# 08_Power_Switch.net
KiCad netlist of a schematic drawn in Altium Designer
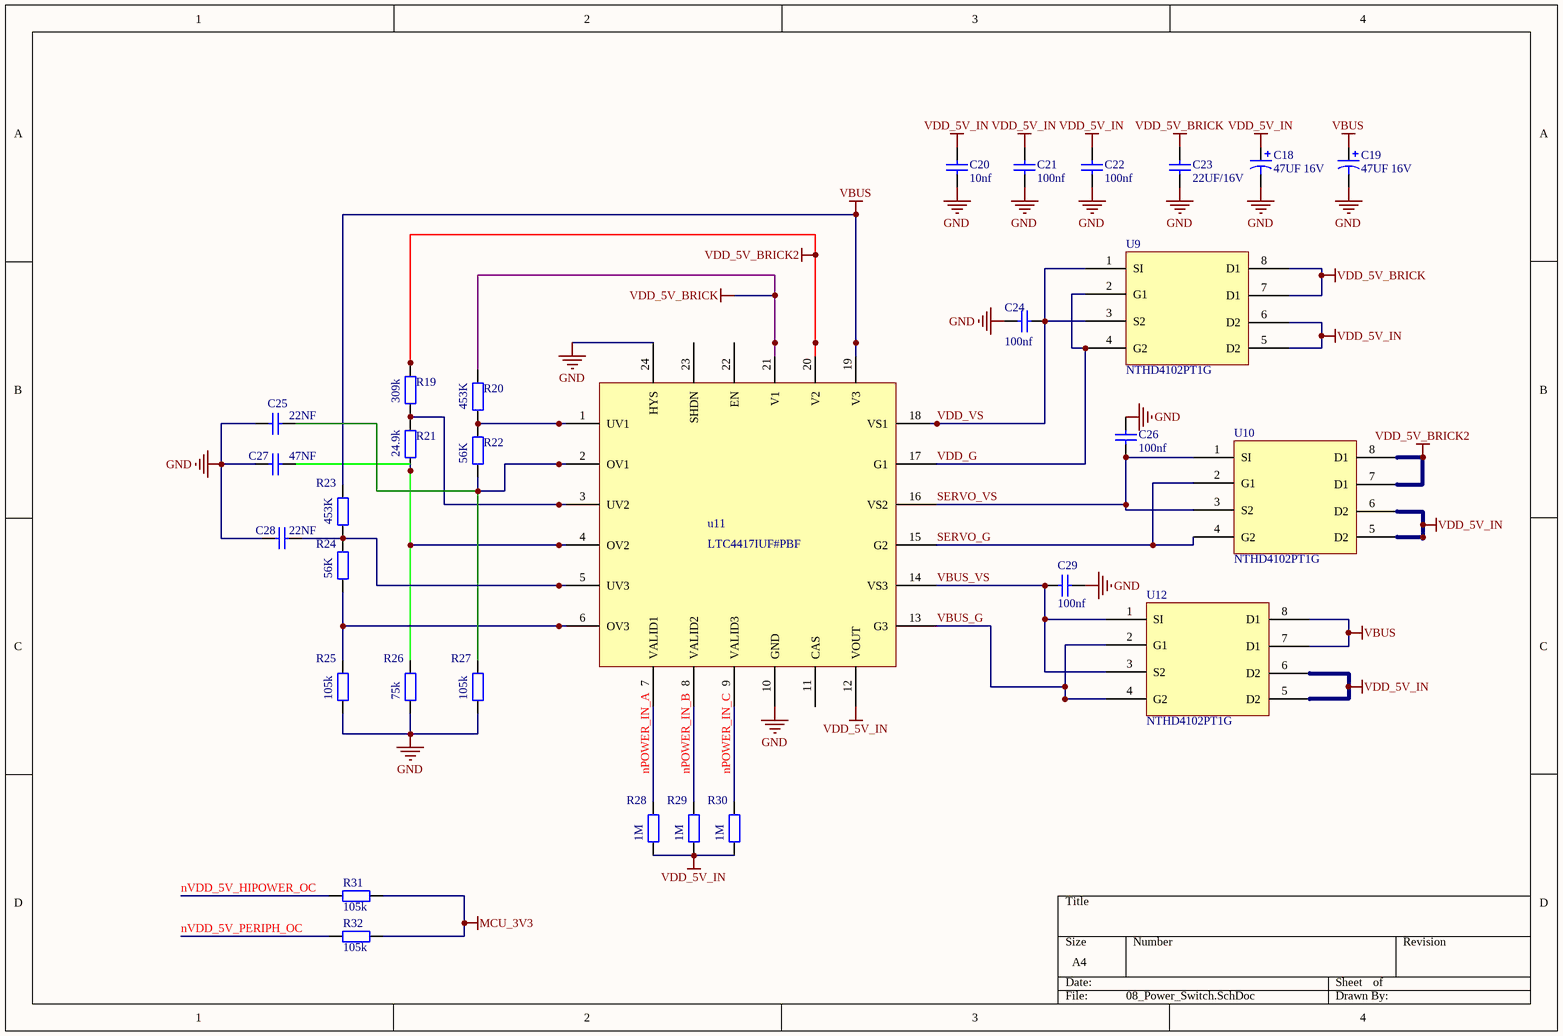
[diagram p0: 08_Power_Switch.SchDoc]

(export (version "E")
  (design (tool "Eeschema 10.0.6"))
  (components
    (comp (ref "C18")
      (value "47UF 16V")
      (footprint "7343CAP")
      (description "Polarized Capacitor (Radial)")
      (fields (field (name "PUBLISHER") "Altium Limited"))
      (libsource (lib "Miscellaneous Devices") (part "Cap Pol1"))
    )
    (comp (ref "C19")
      (value "47UF 16V")
      (footprint "7343CAP")
      (description "Polarized Capacitor (Radial)")
      (fields (field (name "PUBLISHER") "Altium Limited"))
      (libsource (lib "Miscellaneous Devices") (part "Cap Pol1"))
    )
    (comp (ref "C20")
      (value "10nf")
      (fields (field (name "PUBLISHER") "Altium Limited"))
      (libsource (lib "Miscellaneous Devices") (part "Cap"))
    )
    (comp (ref "C21")
      (value "100nf")
      (fields (field (name "PUBLISHER") "Altium Limited"))
      (libsource (lib "Miscellaneous Devices") (part "Cap"))
    )
    (comp (ref "C22")
      (value "100nf")
      (fields (field (name "PUBLISHER") "Altium Limited"))
      (libsource (lib "Miscellaneous Devices") (part "Cap"))
    )
    (comp (ref "C23")
      (value "22UF/16V")
      (fields (field (name "PUBLISHER") "Altium Limited"))
      (libsource (lib "Miscellaneous Devices") (part "Cap"))
    )
    (comp (ref "C24")
      (value "100nf")
      (fields (field (name "PUBLISHER") "Altium Limited"))
      (libsource (lib "Miscellaneous Devices") (part "Cap"))
    )
    (comp (ref "C25")
      (value "22NF")
      (fields (field (name "PUBLISHER") "Altium Limited"))
      (libsource (lib "Miscellaneous Devices") (part "Cap"))
    )
    (comp (ref "C26")
      (value "100nf")
      (fields (field (name "PUBLISHER") "Altium Limited"))
      (libsource (lib "Miscellaneous Devices") (part "Cap"))
    )
    (comp (ref "C27")
      (value "47NF")
      (fields (field (name "PUBLISHER") "Altium Limited"))
      (libsource (lib "Miscellaneous Devices") (part "Cap"))
    )
    (comp (ref "C28")
      (value "22NF")
      (fields (field (name "PUBLISHER") "Altium Limited"))
      (libsource (lib "Miscellaneous Devices") (part "Cap"))
    )
    (comp (ref "C29")
      (value "100nf")
      (fields (field (name "PUBLISHER") "Altium Limited"))
      (libsource (lib "Miscellaneous Devices") (part "Cap"))
    )
    (comp (ref "R19")
      (value "309k")
      (description "Resistor")
      (fields (field (name "PUBLISHER") "Altium Limited"))
      (libsource (lib "Miscellaneous Devices") (part "Res2"))
    )
    (comp (ref "R20")
      (value "453K")
      (description "Resistor")
      (fields (field (name "PUBLISHER") "Altium Limited"))
      (libsource (lib "Miscellaneous Devices") (part "Res2"))
    )
    (comp (ref "R21")
      (value "24.9k")
      (description "Resistor")
      (fields (field (name "PUBLISHER") "Altium Limited"))
      (libsource (lib "Miscellaneous Devices") (part "Res2"))
    )
    (comp (ref "R22")
      (value "56K")
      (description "Resistor")
      (fields (field (name "PUBLISHER") "Altium Limited"))
      (libsource (lib "Miscellaneous Devices") (part "Res2"))
    )
    (comp (ref "R23")
      (value "453K")
      (description "Resistor")
      (fields (field (name "PUBLISHER") "Altium Limited"))
      (libsource (lib "Miscellaneous Devices") (part "Res2"))
    )
    (comp (ref "R24")
      (value "56K")
      (description "Resistor")
      (fields (field (name "PUBLISHER") "Altium Limited"))
      (libsource (lib "Miscellaneous Devices") (part "Res2"))
    )
    (comp (ref "R25")
      (value "105k")
      (description "Resistor")
      (fields (field (name "PUBLISHER") "Altium Limited"))
      (libsource (lib "Miscellaneous Devices") (part "Res2"))
    )
    (comp (ref "R26")
      (value "75k")
      (description "Resistor")
      (fields (field (name "PUBLISHER") "Altium Limited"))
      (libsource (lib "Miscellaneous Devices") (part "Res2"))
    )
    (comp (ref "R27")
      (value "105k")
      (description "Resistor")
      (fields (field (name "PUBLISHER") "Altium Limited"))
      (libsource (lib "Miscellaneous Devices") (part "Res2"))
    )
    (comp (ref "R28")
      (value "1M")
      (description "Resistor")
      (fields (field (name "PUBLISHER") "Altium Limited"))
      (libsource (lib "Miscellaneous Devices") (part "Res2"))
    )
    (comp (ref "R29")
      (value "1M")
      (description "Resistor")
      (fields (field (name "PUBLISHER") "Altium Limited"))
      (libsource (lib "Miscellaneous Devices") (part "Res2"))
    )
    (comp (ref "R30")
      (value "1M")
      (description "Resistor")
      (fields (field (name "PUBLISHER") "Altium Limited"))
      (libsource (lib "Miscellaneous Devices") (part "Res2"))
    )
    (comp (ref "R31")
      (value "105k")
      (description "Resistor")
      (fields (field (name "PUBLISHER") "Altium Limited"))
      (libsource (lib "") (part "Res2_1"))
    )
    (comp (ref "R32")
      (value "105k")
      (description "Resistor")
      (fields (field (name "PUBLISHER") "Altium Limited"))
      (libsource (lib "") (part "Res2_1"))
    )
    (comp (ref "U9")
      (value "NTHD4102PT1G")
      (footprint "1206-8")
      (libsource (lib "hack") (part "NTHD4102PT1G"))
    )
    (comp (ref "U10")
      (value "NTHD4102PT1G")
      (footprint "1206-8")
      (libsource (lib "hack") (part "NTHD4102PT1G"))
    )
    (comp (ref "u11")
      (value "LTC4417IUF#PBF")
      (footprint "QFN24")
      (libsource (lib "hack") (part "LTC4417IUF#PBF"))
    )
    (comp (ref "U12")
      (value "NTHD4102PT1G")
      (footprint "1206-8")
      (libsource (lib "hack") (part "NTHD4102PT1G"))
    )
  )
  (nets
    (net (code "1") (name "/SERVO_G") (class "Default")
      (node (ref "U10") (pin "2") (pinfunction "G1_2") (pintype "passive"))
      (node (ref "U10") (pin "4") (pinfunction "G2_4") (pintype "passive"))
      (node (ref "u11") (pin "15") (pinfunction "G2_15") (pintype "passive"))
    )
    (net (code "2") (name "/SERVO_VS") (class "Default")
      (node (ref "C26") (pin "1") (pinfunction "1_1") (pintype "passive"))
      (node (ref "U10") (pin "1") (pinfunction "SI_1") (pintype "passive"))
      (node (ref "U10") (pin "3") (pinfunction "S2_3") (pintype "passive"))
      (node (ref "u11") (pin "16") (pinfunction "VS2_16") (pintype "passive"))
    )
    (net (code "3") (name "/VBUS_G") (class "Default")
      (node (ref "U12") (pin "2") (pinfunction "G1_2") (pintype "passive"))
      (node (ref "U12") (pin "4") (pinfunction "G2_4") (pintype "passive"))
      (node (ref "u11") (pin "13") (pinfunction "G3_13") (pintype "passive"))
    )
    (net (code "4") (name "/VBUS_VS") (class "Default")
      (node (ref "C29") (pin "1") (pinfunction "1_1") (pintype "passive"))
      (node (ref "U12") (pin "1") (pinfunction "SI_1") (pintype "passive"))
      (node (ref "U12") (pin "3") (pinfunction "S2_3") (pintype "passive"))
      (node (ref "u11") (pin "14") (pinfunction "VS3_14") (pintype "passive"))
    )
    (net (code "5") (name "/VDD_G") (class "Default")
      (node (ref "U9") (pin "2") (pinfunction "G1_2") (pintype "passive"))
      (node (ref "U9") (pin "4") (pinfunction "G2_4") (pintype "passive"))
      (node (ref "u11") (pin "17") (pinfunction "G1_17") (pintype "passive"))
    )
    (net (code "6") (name "/VDD_VS") (class "Default")
      (node (ref "C24") (pin "1") (pinfunction "1_1") (pintype "passive"))
      (node (ref "U9") (pin "1") (pinfunction "SI_1") (pintype "passive"))
      (node (ref "U9") (pin "3") (pinfunction "S2_3") (pintype "passive"))
      (node (ref "u11") (pin "18") (pinfunction "VS1_18") (pintype "passive"))
    )
    (net (code "7") (name "/nPOWER_IN_A") (class "Default")
      (node (ref "R28") (pin "2") (pinfunction "2_2") (pintype "passive"))
      (node (ref "u11") (pin "7") (pinfunction "VALID1_7") (pintype "passive"))
    )
    (net (code "8") (name "/nPOWER_IN_B") (class "Default")
      (node (ref "R29") (pin "2") (pinfunction "2_2") (pintype "passive"))
      (node (ref "u11") (pin "8") (pinfunction "VALID2_8") (pintype "passive"))
    )
    (net (code "9") (name "/nPOWER_IN_C") (class "Default")
      (node (ref "R30") (pin "2") (pinfunction "2_2") (pintype "passive"))
      (node (ref "u11") (pin "9") (pinfunction "VALID3_9") (pintype "passive"))
    )
    (net (code "10") (name "/nVDD_5V_HIPOWER_OC") (class "Default")
      (node (ref "R31") (pin "1") (pinfunction "1_1") (pintype "passive"))
    )
    (net (code "11") (name "/nVDD_5V_PERIPH_OC") (class "Default")
      (node (ref "R32") (pin "1") (pinfunction "1_1") (pintype "passive"))
    )
    (net (code "12") (name "GND") (class "Default")
      (node (ref "C18") (pin "C") (pinfunction "2_C") (pintype "passive"))
      (node (ref "C19") (pin "C") (pinfunction "2_C") (pintype "passive"))
      (node (ref "C20") (pin "1") (pinfunction "1_1") (pintype "passive"))
      (node (ref "C21") (pin "1") (pinfunction "1_1") (pintype "passive"))
      (node (ref "C22") (pin "1") (pinfunction "1_1") (pintype "passive"))
      (node (ref "C23") (pin "1") (pinfunction "1_1") (pintype "passive"))
      (node (ref "C24") (pin "2") (pinfunction "2_2") (pintype "passive"))
      (node (ref "C25") (pin "2") (pinfunction "2_2") (pintype "passive"))
      (node (ref "C26") (pin "2") (pinfunction "2_2") (pintype "passive"))
      (node (ref "C27") (pin "2") (pinfunction "2_2") (pintype "passive"))
      (node (ref "C28") (pin "2") (pinfunction "2_2") (pintype "passive"))
      (node (ref "C29") (pin "2") (pinfunction "2_2") (pintype "passive"))
      (node (ref "R25") (pin "1") (pinfunction "1_1") (pintype "passive"))
      (node (ref "R26") (pin "1") (pinfunction "1_1") (pintype "passive"))
      (node (ref "R27") (pin "1") (pinfunction "1_1") (pintype "passive"))
      (node (ref "u11") (pin "10") (pinfunction "GND_10") (pintype "passive"))
      (node (ref "u11") (pin "24") (pinfunction "HYS_24") (pintype "passive"))
    )
    (net (code "13") (name "MCU_3V3") (class "Default")
      (node (ref "R31") (pin "2") (pinfunction "2_2") (pintype "passive"))
      (node (ref "R32") (pin "2") (pinfunction "2_2") (pintype "passive"))
    )
    (net (code "14") (name "Net-(u11-OV1)") (class "Default")
      (node (ref "C25") (pin "1") (pinfunction "1_1") (pintype "passive"))
      (node (ref "R22") (pin "1") (pinfunction "1_1") (pintype "passive"))
      (node (ref "R27") (pin "2") (pinfunction "2_2") (pintype "passive"))
      (node (ref "u11") (pin "2") (pinfunction "OV1_2") (pintype "passive"))
    )
    (net (code "15") (name "Net-(u11-OV2)") (class "Default")
      (node (ref "C27") (pin "1") (pinfunction "1_1") (pintype "passive"))
      (node (ref "R21") (pin "1") (pinfunction "1_1") (pintype "passive"))
      (node (ref "R26") (pin "2") (pinfunction "2_2") (pintype "passive"))
      (node (ref "u11") (pin "4") (pinfunction "OV2_4") (pintype "passive"))
    )
    (net (code "16") (name "Net-(u11-OV3)") (class "Default")
      (node (ref "R24") (pin "1") (pinfunction "1_1") (pintype "passive"))
      (node (ref "R25") (pin "2") (pinfunction "2_2") (pintype "passive"))
      (node (ref "u11") (pin "6") (pinfunction "OV3_6") (pintype "passive"))
    )
    (net (code "17") (name "Net-(u11-UV1)") (class "Default")
      (node (ref "R20") (pin "1") (pinfunction "1_1") (pintype "passive"))
      (node (ref "R22") (pin "2") (pinfunction "2_2") (pintype "passive"))
      (node (ref "u11") (pin "1") (pinfunction "UV1_1") (pintype "passive"))
    )
    (net (code "18") (name "Net-(u11-UV2)") (class "Default")
      (node (ref "R19") (pin "1") (pinfunction "1_1") (pintype "passive"))
      (node (ref "R21") (pin "2") (pinfunction "2_2") (pintype "passive"))
      (node (ref "u11") (pin "3") (pinfunction "UV2_3") (pintype "passive"))
    )
    (net (code "19") (name "Net-(u11-UV3)") (class "Default")
      (node (ref "C28") (pin "1") (pinfunction "1_1") (pintype "passive"))
      (node (ref "R23") (pin "1") (pinfunction "1_1") (pintype "passive"))
      (node (ref "R24") (pin "2") (pinfunction "2_2") (pintype "passive"))
      (node (ref "u11") (pin "5") (pinfunction "UV3_5") (pintype "passive"))
    )
    (net (code "20") (name "VBUS") (class "Default")
      (node (ref "C19") (pin "A") (pinfunction "1_A") (pintype "passive"))
      (node (ref "R23") (pin "2") (pinfunction "2_2") (pintype "passive"))
      (node (ref "U12") (pin "7") (pinfunction "D1_7") (pintype "passive"))
      (node (ref "U12") (pin "8") (pinfunction "D1_8") (pintype "passive"))
      (node (ref "u11") (pin "19") (pinfunction "V3_19") (pintype "passive"))
    )
    (net (code "21") (name "VDD_5V_BRICK") (class "Default")
      (node (ref "C23") (pin "2") (pinfunction "2_2") (pintype "passive"))
      (node (ref "R20") (pin "2") (pinfunction "2_2") (pintype "passive"))
      (node (ref "U9") (pin "7") (pinfunction "D1_7") (pintype "passive"))
      (node (ref "U9") (pin "8") (pinfunction "D1_8") (pintype "passive"))
      (node (ref "u11") (pin "21") (pinfunction "V1_21") (pintype "passive"))
    )
    (net (code "22") (name "VDD_5V_BRICK2") (class "Default")
      (node (ref "R19") (pin "2") (pinfunction "2_2") (pintype "passive"))
      (node (ref "U10") (pin "7") (pinfunction "D1_7") (pintype "passive"))
      (node (ref "U10") (pin "8") (pinfunction "D1_8") (pintype "passive"))
      (node (ref "u11") (pin "20") (pinfunction "V2_20") (pintype "passive"))
    )
    (net (code "23") (name "VDD_5V_IN") (class "Default")
      (node (ref "C18") (pin "A") (pinfunction "1_A") (pintype "passive"))
      (node (ref "C20") (pin "2") (pinfunction "2_2") (pintype "passive"))
      (node (ref "C21") (pin "2") (pinfunction "2_2") (pintype "passive"))
      (node (ref "C22") (pin "2") (pinfunction "2_2") (pintype "passive"))
      (node (ref "R28") (pin "1") (pinfunction "1_1") (pintype "passive"))
      (node (ref "R29") (pin "1") (pinfunction "1_1") (pintype "passive"))
      (node (ref "R30") (pin "1") (pinfunction "1_1") (pintype "passive"))
      (node (ref "U10") (pin "5") (pinfunction "D2_5") (pintype "passive"))
      (node (ref "U10") (pin "6") (pinfunction "D2_6") (pintype "passive"))
      (node (ref "U12") (pin "5") (pinfunction "D2_5") (pintype "passive"))
      (node (ref "U12") (pin "6") (pinfunction "D2_6") (pintype "passive"))
      (node (ref "U9") (pin "5") (pinfunction "D2_5") (pintype "passive"))
      (node (ref "U9") (pin "6") (pinfunction "D2_6") (pintype "passive"))
      (node (ref "u11") (pin "12") (pinfunction "VOUT_12") (pintype "passive"))
    )
    (net (code "24") (name "unconnected-(u11-CAS-Pad11)") (class "Default")
      (node (ref "u11") (pin "11") (pinfunction "CAS_11") (pintype "passive"))
    )
    (net (code "25") (name "unconnected-(u11-EN-Pad22)") (class "Default")
      (node (ref "u11") (pin "22") (pinfunction "EN_22") (pintype "passive"))
    )
    (net (code "26") (name "unconnected-(u11-SHDN-Pad23)") (class "Default")
      (node (ref "u11") (pin "23") (pinfunction "SHDN_23") (pintype "passive"))
    )
  )
)
